# ArduinoNanoShield.net
KiCad netlist of a schematic drawn in EAGLE
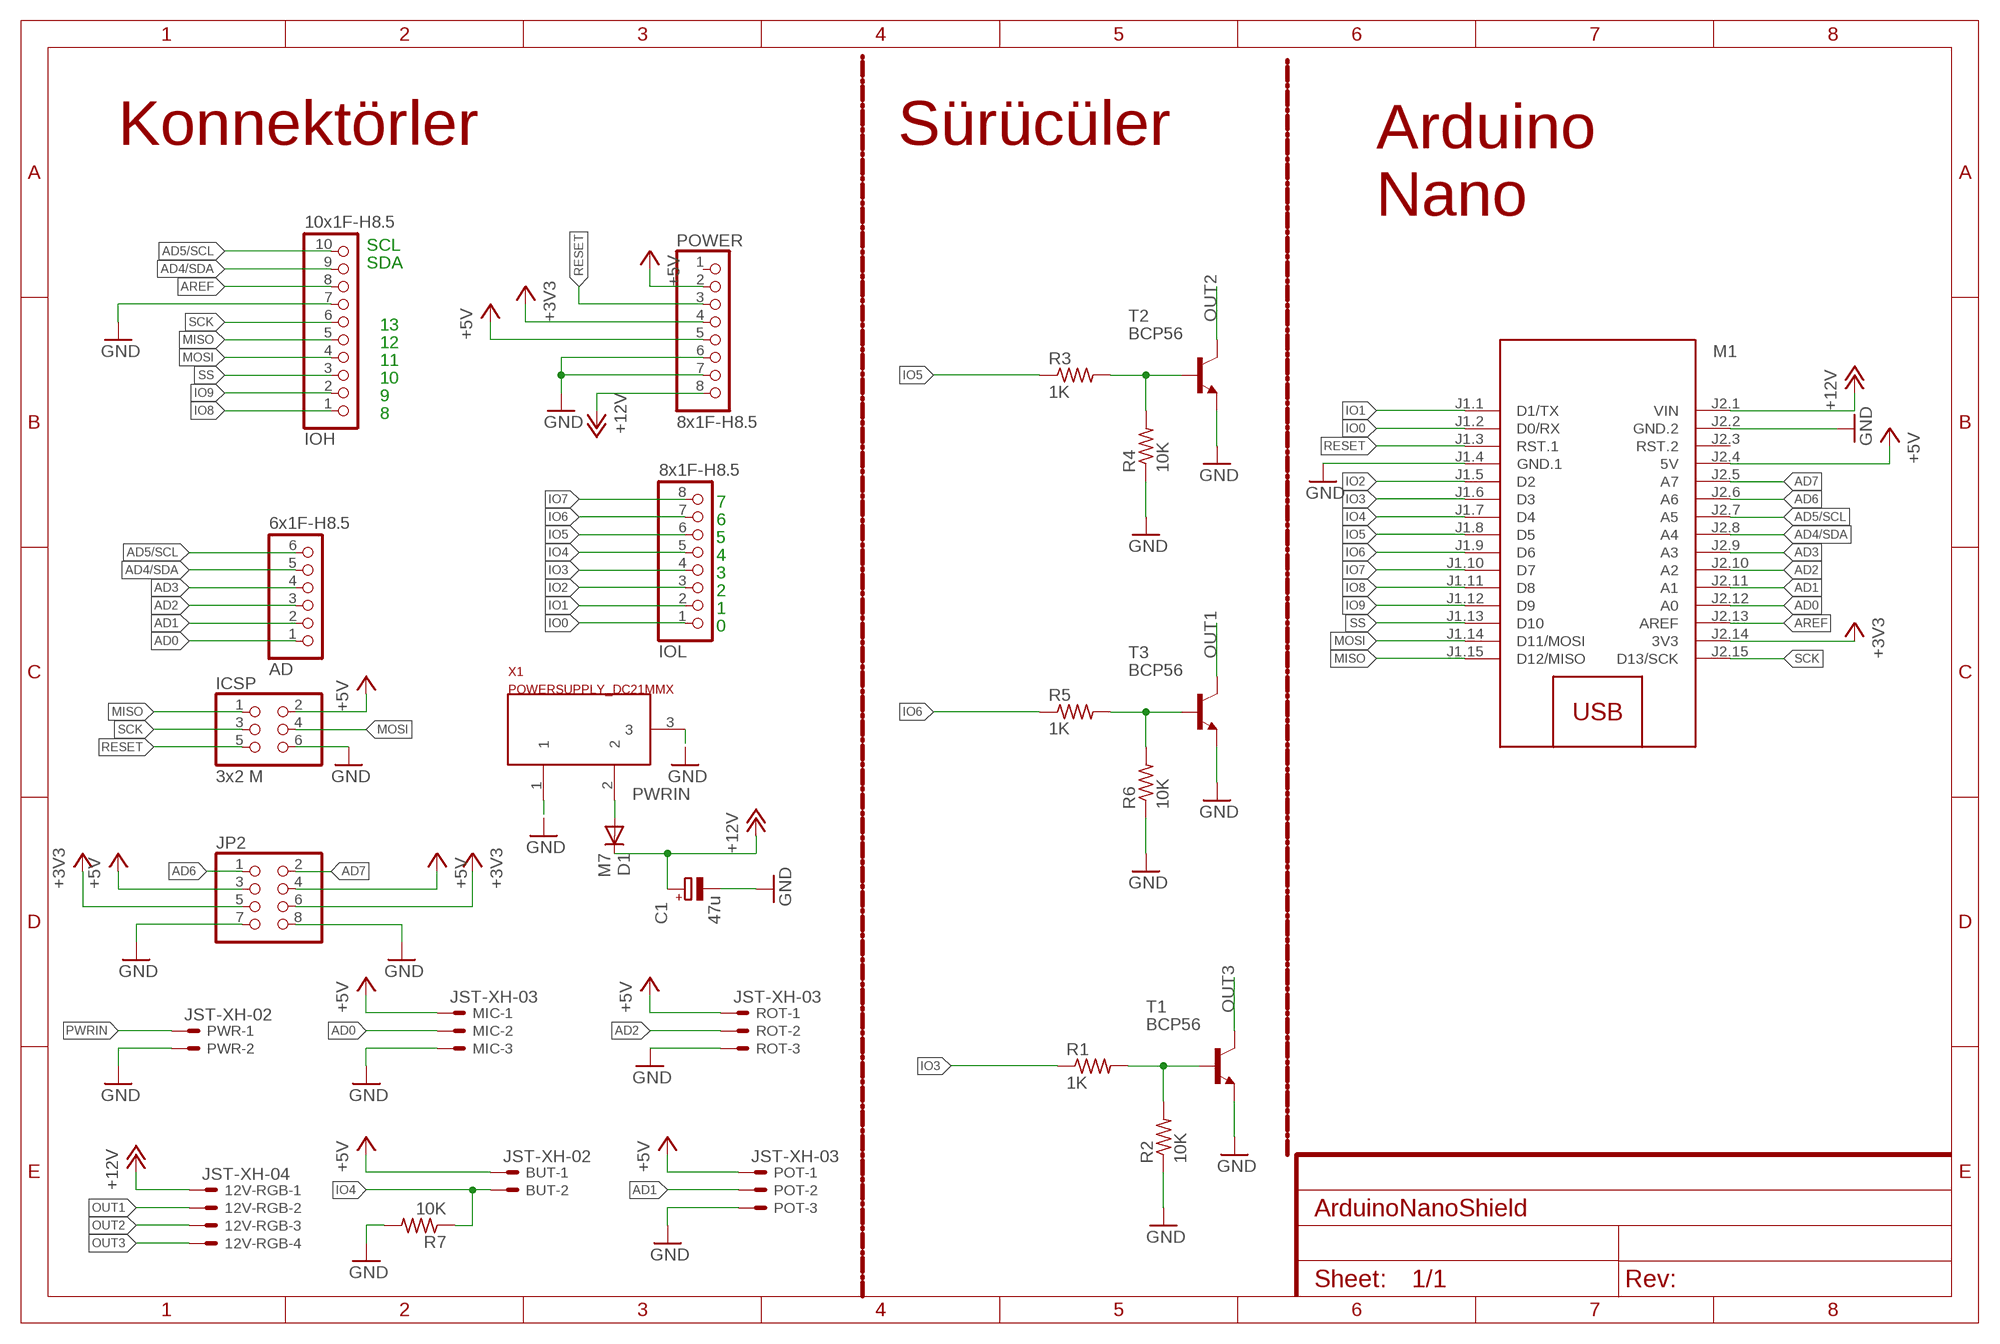
[diagram p0: schematic, sheet 1]

(export (version "E")
  (design (tool "Eeschema 10.0.6"))
  (components
    (comp (ref "12V-RGB")
      (value "JST-XH-04")
      (footprint "eagle-import:JST-XH-04-PACKAGE-ROUND-PAD")
      (libsource (lib "eagle-import") (part "JST-XH-04-PIN-ROUND-PAD"))
    )
    (comp (ref "AD")
      (value "6x1F-H8.5")
      (footprint "eagle-import:1X06")
      (libsource (lib "eagle-import") (part "PINHD-1X6"))
    )
    (comp (ref "BUT")
      (value "JST-XH-02")
      (footprint "eagle-import:JST-XH-02-PACKAGE-ROUND-PAD")
      (libsource (lib "eagle-import") (part "JST-XH-02-PIN-ROUND-PAD"))
    )
    (comp (ref "C1")
      (value "47u")
      (footprint "eagle-import:PANASONIC_D")
      (libsource (lib "eagle-import") (part "CPOL-EUD"))
    )
    (comp (ref "D1")
      (value "M7")
      (footprint "eagle-import:SMB")
      (libsource (lib "eagle-import") (part "DIODE-SMB"))
    )
    (comp (ref "ICSP")
      (value "3x2 M")
      (footprint "eagle-import:2X03")
      (libsource (lib "eagle-import") (part "PINHD-2X3"))
    )
    (comp (ref "IOH")
      (value "10x1F-H8.5")
      (footprint "eagle-import:1X10")
      (libsource (lib "eagle-import") (part "PINHD-1X10_ARD"))
    )
    (comp (ref "IOL")
      (value "8x1F-H8.5")
      (footprint "eagle-import:1X08")
      (libsource (lib "eagle-import") (part "PINHD-1X8"))
    )
    (comp (ref "JP2")
      (value "PINHD-2X4")
      (footprint "eagle-import:2X04")
      (libsource (lib "eagle-import") (part "PINHD-2X4"))
    )
    (comp (ref "M1")
      (value "ARDUINO-NANO")
      (footprint "eagle-import:ARDUINO-NANO")
      (libsource (lib "eagle-import") (part "ARDUINO-NANO"))
    )
    (comp (ref "MIC")
      (value "JST-XH-03")
      (footprint "eagle-import:JST-XH-03-PACKAGE-ROUND-PAD")
      (libsource (lib "eagle-import") (part "JST-XH-03-PIN-ROUND-PAD"))
    )
    (comp (ref "POT")
      (value "JST-XH-03")
      (footprint "eagle-import:JST-XH-03-PACKAGE-ROUND-PAD")
      (libsource (lib "eagle-import") (part "JST-XH-03-PIN-ROUND-PAD"))
    )
    (comp (ref "POWER")
      (value "8x1F-H8.5")
      (footprint "eagle-import:1X08")
      (libsource (lib "eagle-import") (part "PINHD-1X8"))
    )
    (comp (ref "PWR")
      (value "JST-XH-02")
      (footprint "eagle-import:JST-XH-02-PACKAGE-ROUND-PAD")
      (libsource (lib "eagle-import") (part "JST-XH-02-PIN-ROUND-PAD"))
    )
    (comp (ref "R1")
      (value "1K")
      (footprint "eagle-import:M0805")
      (libsource (lib "eagle-import") (part "R-US_M0805"))
    )
    (comp (ref "R2")
      (value "10K")
      (footprint "eagle-import:M0805")
      (libsource (lib "eagle-import") (part "R-US_M0805"))
    )
    (comp (ref "R3")
      (value "1K")
      (footprint "eagle-import:M0805")
      (libsource (lib "eagle-import") (part "R-US_M0805"))
    )
    (comp (ref "R4")
      (value "10K")
      (footprint "eagle-import:M0805")
      (libsource (lib "eagle-import") (part "R-US_M0805"))
    )
    (comp (ref "R5")
      (value "1K")
      (footprint "eagle-import:M0805")
      (libsource (lib "eagle-import") (part "R-US_M0805"))
    )
    (comp (ref "R6")
      (value "10K")
      (footprint "eagle-import:M0805")
      (libsource (lib "eagle-import") (part "R-US_M0805"))
    )
    (comp (ref "R7")
      (value "10K")
      (footprint "eagle-import:M0805")
      (libsource (lib "eagle-import") (part "R-US_M0805"))
    )
    (comp (ref "ROT")
      (value "JST-XH-03")
      (footprint "eagle-import:JST-XH-03-PACKAGE-ROUND-PAD")
      (libsource (lib "eagle-import") (part "JST-XH-03-PIN-ROUND-PAD"))
    )
    (comp (ref "T1")
      (value "BCP56")
      (footprint "eagle-import:SOT223")
      (libsource (lib "eagle-import") (part "-NPN-SOT223PZT2222A"))
    )
    (comp (ref "T2")
      (value "BCP56")
      (footprint "eagle-import:SOT223")
      (libsource (lib "eagle-import") (part "-NPN-SOT223PZT2222A"))
    )
    (comp (ref "T3")
      (value "BCP56")
      (footprint "eagle-import:SOT223")
      (libsource (lib "eagle-import") (part "-NPN-SOT223PZT2222A"))
    )
    (comp (ref "X1")
      (value "POWERSUPPLY_DC21MMX")
      (footprint "eagle-import:POWERSUPPLY_DC-21MM")
      (libsource (lib "eagle-import") (part "POWERSUPPLY_DC21MMX"))
    )
  )
  (nets
    (net (code "1") (name "+3V3") (class "Default")
      (node (ref "JP2") (pin "5") (pinfunction "5_5") (pintype "passive"))
      (node (ref "JP2") (pin "6") (pinfunction "6_6") (pintype "passive"))
      (node (ref "M1") (pin "J2.14") (pinfunction "3V3_J2.14") (pintype "power_in"))
      (node (ref "POWER") (pin "4") (pinfunction "4_4") (pintype "passive"))
    )
    (net (code "2") (name "+5V") (class "Default")
      (node (ref "BUT") (pin "1") (pinfunction "S_1") (pintype "passive"))
      (node (ref "ICSP") (pin "2") (pinfunction "2_2") (pintype "passive"))
      (node (ref "JP2") (pin "3") (pinfunction "3_3") (pintype "passive"))
      (node (ref "JP2") (pin "4") (pinfunction "4_4") (pintype "passive"))
      (node (ref "M1") (pin "J2.4") (pinfunction "5V_J2.4") (pintype "power_in"))
      (node (ref "MIC") (pin "1") (pinfunction "S_1") (pintype "passive"))
      (node (ref "POT") (pin "1") (pinfunction "S_1") (pintype "passive"))
      (node (ref "POWER") (pin "2") (pinfunction "2_2") (pintype "passive"))
      (node (ref "POWER") (pin "5") (pinfunction "5_5") (pintype "passive"))
      (node (ref "ROT") (pin "1") (pinfunction "S_1") (pintype "passive"))
    )
    (net (code "3") (name "+12V") (class "Default")
      (node (ref "12V-RGB") (pin "1") (pinfunction "S_1") (pintype "passive"))
      (node (ref "C1") (pin "+") (pinfunction "+_+") (pintype "passive"))
      (node (ref "D1") (pin "C") (pinfunction "C_C") (pintype "passive"))
      (node (ref "M1") (pin "J2.1") (pinfunction "VIN_J2.1") (pintype "power_in"))
      (node (ref "POWER") (pin "8") (pinfunction "8_8") (pintype "passive"))
    )
    (net (code "4") (name "AD0") (class "Default")
      (node (ref "AD") (pin "1") (pinfunction "1_1") (pintype "passive"))
      (node (ref "M1") (pin "J2.12") (pinfunction "A0_J2.12") (pintype "bidirectional"))
      (node (ref "MIC") (pin "2") (pinfunction "S_2") (pintype "passive"))
    )
    (net (code "5") (name "AD1") (class "Default")
      (node (ref "AD") (pin "2") (pinfunction "2_2") (pintype "passive"))
      (node (ref "M1") (pin "J2.11") (pinfunction "A1_J2.11") (pintype "bidirectional"))
      (node (ref "POT") (pin "2") (pinfunction "S_2") (pintype "passive"))
    )
    (net (code "6") (name "AD2") (class "Default")
      (node (ref "AD") (pin "3") (pinfunction "3_3") (pintype "passive"))
      (node (ref "M1") (pin "J2.10") (pinfunction "A2_J2.10") (pintype "bidirectional"))
      (node (ref "ROT") (pin "2") (pinfunction "S_2") (pintype "passive"))
    )
    (net (code "7") (name "AD3") (class "Default")
      (node (ref "AD") (pin "4") (pinfunction "4_4") (pintype "passive"))
      (node (ref "M1") (pin "J2.9") (pinfunction "A3_J2.9") (pintype "bidirectional"))
    )
    (net (code "8") (name "AD4{slash}SDA") (class "Default")
      (node (ref "AD") (pin "5") (pinfunction "5_5") (pintype "passive"))
      (node (ref "IOH") (pin "9") (pinfunction "9_9") (pintype "passive"))
      (node (ref "M1") (pin "J2.8") (pinfunction "A4_J2.8") (pintype "bidirectional"))
    )
    (net (code "9") (name "AD5{slash}SCL") (class "Default")
      (node (ref "AD") (pin "6") (pinfunction "6_6") (pintype "passive"))
      (node (ref "IOH") (pin "10") (pinfunction "10_10") (pintype "passive"))
      (node (ref "M1") (pin "J2.7") (pinfunction "A5_J2.7") (pintype "bidirectional"))
    )
    (net (code "10") (name "AD6") (class "Default")
      (node (ref "JP2") (pin "1") (pinfunction "1_1") (pintype "passive"))
      (node (ref "M1") (pin "J2.6") (pinfunction "A6_J2.6") (pintype "bidirectional"))
    )
    (net (code "11") (name "AD7") (class "Default")
      (node (ref "JP2") (pin "2") (pinfunction "2_2") (pintype "passive"))
      (node (ref "M1") (pin "J2.5") (pinfunction "A7_J2.5") (pintype "bidirectional"))
    )
    (net (code "12") (name "AREF") (class "Default")
      (node (ref "IOH") (pin "8") (pinfunction "8_8") (pintype "passive"))
      (node (ref "M1") (pin "J2.13") (pinfunction "AREF_J2.13") (pintype "bidirectional"))
    )
    (net (code "13") (name "GND") (class "Default")
      (node (ref "C1") (pin "-") (pinfunction "-_-") (pintype "passive"))
      (node (ref "ICSP") (pin "6") (pinfunction "6_6") (pintype "passive"))
      (node (ref "IOH") (pin "7") (pinfunction "7_7") (pintype "passive"))
      (node (ref "JP2") (pin "7") (pinfunction "7_7") (pintype "passive"))
      (node (ref "JP2") (pin "8") (pinfunction "8_8") (pintype "passive"))
      (node (ref "M1") (pin "J1.4") (pinfunction "GND.1_J1.4") (pintype "power_in"))
      (node (ref "M1") (pin "J2.2") (pinfunction "GND.2_J2.2") (pintype "power_in"))
      (node (ref "MIC") (pin "3") (pinfunction "S_3") (pintype "passive"))
      (node (ref "POT") (pin "3") (pinfunction "S_3") (pintype "passive"))
      (node (ref "POWER") (pin "6") (pinfunction "6_6") (pintype "passive"))
      (node (ref "POWER") (pin "7") (pinfunction "7_7") (pintype "passive"))
      (node (ref "PWR") (pin "2") (pinfunction "S_2") (pintype "passive"))
      (node (ref "R2") (pin "1") (pinfunction "1_1") (pintype "passive"))
      (node (ref "R4") (pin "1") (pinfunction "1_1") (pintype "passive"))
      (node (ref "R6") (pin "1") (pinfunction "1_1") (pintype "passive"))
      (node (ref "R7") (pin "2") (pinfunction "2_2") (pintype "passive"))
      (node (ref "ROT") (pin "3") (pinfunction "S_3") (pintype "passive"))
      (node (ref "T1") (pin "3") (pinfunction "E_3") (pintype "passive"))
      (node (ref "T2") (pin "3") (pinfunction "E_3") (pintype "passive"))
      (node (ref "T3") (pin "3") (pinfunction "E_3") (pintype "passive"))
      (node (ref "X1") (pin "1") (pinfunction "1_1") (pintype "power_in"))
      (node (ref "X1") (pin "3") (pinfunction "3_3") (pintype "power_in"))
    )
    (net (code "14") (name "IO0") (class "Default")
      (node (ref "IOL") (pin "1") (pinfunction "1_1") (pintype "passive"))
      (node (ref "M1") (pin "J1.2") (pinfunction "D0/RX_J1.2") (pintype "bidirectional"))
    )
    (net (code "15") (name "IO1") (class "Default")
      (node (ref "IOL") (pin "2") (pinfunction "2_2") (pintype "passive"))
      (node (ref "M1") (pin "J1.1") (pinfunction "D1/TX_J1.1") (pintype "bidirectional"))
    )
    (net (code "16") (name "IO2") (class "Default")
      (node (ref "IOL") (pin "3") (pinfunction "3_3") (pintype "passive"))
      (node (ref "M1") (pin "J1.5") (pinfunction "D2_J1.5") (pintype "bidirectional"))
    )
    (net (code "17") (name "IO3") (class "Default")
      (node (ref "IOL") (pin "4") (pinfunction "4_4") (pintype "passive"))
      (node (ref "M1") (pin "J1.6") (pinfunction "D3_J1.6") (pintype "bidirectional"))
      (node (ref "R1") (pin "1") (pinfunction "1_1") (pintype "passive"))
    )
    (net (code "18") (name "IO4") (class "Default")
      (node (ref "BUT") (pin "2") (pinfunction "S_2") (pintype "passive"))
      (node (ref "IOL") (pin "5") (pinfunction "5_5") (pintype "passive"))
      (node (ref "M1") (pin "J1.7") (pinfunction "D4_J1.7") (pintype "bidirectional"))
      (node (ref "R7") (pin "1") (pinfunction "1_1") (pintype "passive"))
    )
    (net (code "19") (name "IO5") (class "Default")
      (node (ref "IOL") (pin "6") (pinfunction "6_6") (pintype "passive"))
      (node (ref "M1") (pin "J1.8") (pinfunction "D5_J1.8") (pintype "bidirectional"))
      (node (ref "R3") (pin "1") (pinfunction "1_1") (pintype "passive"))
    )
    (net (code "20") (name "IO6") (class "Default")
      (node (ref "IOL") (pin "7") (pinfunction "7_7") (pintype "passive"))
      (node (ref "M1") (pin "J1.9") (pinfunction "D6_J1.9") (pintype "bidirectional"))
      (node (ref "R5") (pin "1") (pinfunction "1_1") (pintype "passive"))
    )
    (net (code "21") (name "IO7") (class "Default")
      (node (ref "IOL") (pin "8") (pinfunction "8_8") (pintype "passive"))
      (node (ref "M1") (pin "J1.10") (pinfunction "D7_J1.10") (pintype "bidirectional"))
    )
    (net (code "22") (name "IO8") (class "Default")
      (node (ref "IOH") (pin "1") (pinfunction "1_1") (pintype "passive"))
      (node (ref "M1") (pin "J1.11") (pinfunction "D8_J1.11") (pintype "bidirectional"))
    )
    (net (code "23") (name "IO9") (class "Default")
      (node (ref "IOH") (pin "2") (pinfunction "2_2") (pintype "passive"))
      (node (ref "M1") (pin "J1.12") (pinfunction "D9_J1.12") (pintype "bidirectional"))
    )
    (net (code "24") (name "MISO") (class "Default")
      (node (ref "ICSP") (pin "1") (pinfunction "1_1") (pintype "passive"))
      (node (ref "IOH") (pin "5") (pinfunction "5_5") (pintype "passive"))
      (node (ref "M1") (pin "J1.15") (pinfunction "D12/MISO_J1.15") (pintype "bidirectional"))
    )
    (net (code "25") (name "MOSI") (class "Default")
      (node (ref "ICSP") (pin "4") (pinfunction "4_4") (pintype "passive"))
      (node (ref "IOH") (pin "4") (pinfunction "4_4") (pintype "passive"))
      (node (ref "M1") (pin "J1.14") (pinfunction "D11/MOSI_J1.14") (pintype "bidirectional"))
    )
    (net (code "26") (name "Net-(T1-B)") (class "Default")
      (node (ref "R1") (pin "2") (pinfunction "2_2") (pintype "passive"))
      (node (ref "R2") (pin "2") (pinfunction "2_2") (pintype "passive"))
      (node (ref "T1") (pin "1") (pinfunction "B_1") (pintype "passive"))
    )
    (net (code "27") (name "Net-(T2-B)") (class "Default")
      (node (ref "R3") (pin "2") (pinfunction "2_2") (pintype "passive"))
      (node (ref "R4") (pin "2") (pinfunction "2_2") (pintype "passive"))
      (node (ref "T2") (pin "1") (pinfunction "B_1") (pintype "passive"))
    )
    (net (code "28") (name "Net-(T3-B)") (class "Default")
      (node (ref "R5") (pin "2") (pinfunction "2_2") (pintype "passive"))
      (node (ref "R6") (pin "2") (pinfunction "2_2") (pintype "passive"))
      (node (ref "T3") (pin "1") (pinfunction "B_1") (pintype "passive"))
    )
    (net (code "29") (name "OUT1") (class "Default")
      (node (ref "12V-RGB") (pin "2") (pinfunction "S_2") (pintype "passive"))
      (node (ref "T3") (pin "4") (pinfunction "C_4") (pintype "passive"))
    )
    (net (code "30") (name "OUT2") (class "Default")
      (node (ref "12V-RGB") (pin "3") (pinfunction "S_3") (pintype "passive"))
      (node (ref "T2") (pin "4") (pinfunction "C_4") (pintype "passive"))
    )
    (net (code "31") (name "OUT3") (class "Default")
      (node (ref "12V-RGB") (pin "4") (pinfunction "S_4") (pintype "passive"))
      (node (ref "T1") (pin "4") (pinfunction "C_4") (pintype "passive"))
    )
    (net (code "32") (name "PWRIN") (class "Default")
      (node (ref "D1") (pin "A") (pinfunction "A_A") (pintype "passive"))
      (node (ref "PWR") (pin "1") (pinfunction "S_1") (pintype "passive"))
      (node (ref "X1") (pin "2") (pinfunction "2_2") (pintype "power_in"))
    )
    (net (code "33") (name "RESET") (class "Default")
      (node (ref "ICSP") (pin "5") (pinfunction "5_5") (pintype "passive"))
      (node (ref "M1") (pin "J1.3") (pinfunction "RST.1_J1.3") (pintype "bidirectional"))
      (node (ref "POWER") (pin "3") (pinfunction "3_3") (pintype "passive"))
    )
    (net (code "34") (name "SCK") (class "Default")
      (node (ref "ICSP") (pin "3") (pinfunction "3_3") (pintype "passive"))
      (node (ref "IOH") (pin "6") (pinfunction "6_6") (pintype "passive"))
      (node (ref "M1") (pin "J2.15") (pinfunction "D13/SCK_J2.15") (pintype "bidirectional"))
    )
    (net (code "35") (name "SS") (class "Default")
      (node (ref "IOH") (pin "3") (pinfunction "3_3") (pintype "passive"))
      (node (ref "M1") (pin "J1.13") (pinfunction "D10_J1.13") (pintype "bidirectional"))
    )
    (net (code "36") (name "unconnected-(M1-RST.2-PadJ2.3)") (class "Default")
      (node (ref "M1") (pin "J2.3") (pinfunction "RST.2_J2.3") (pintype "bidirectional"))
    )
    (net (code "37") (name "unconnected-(POWER-Pad1)") (class "Default")
      (node (ref "POWER") (pin "1") (pinfunction "1_1") (pintype "passive"))
    )
  )
)
